# Rollo_APP_TS_V0_3.net
KiCad netlist of a schematic drawn in EAGLE
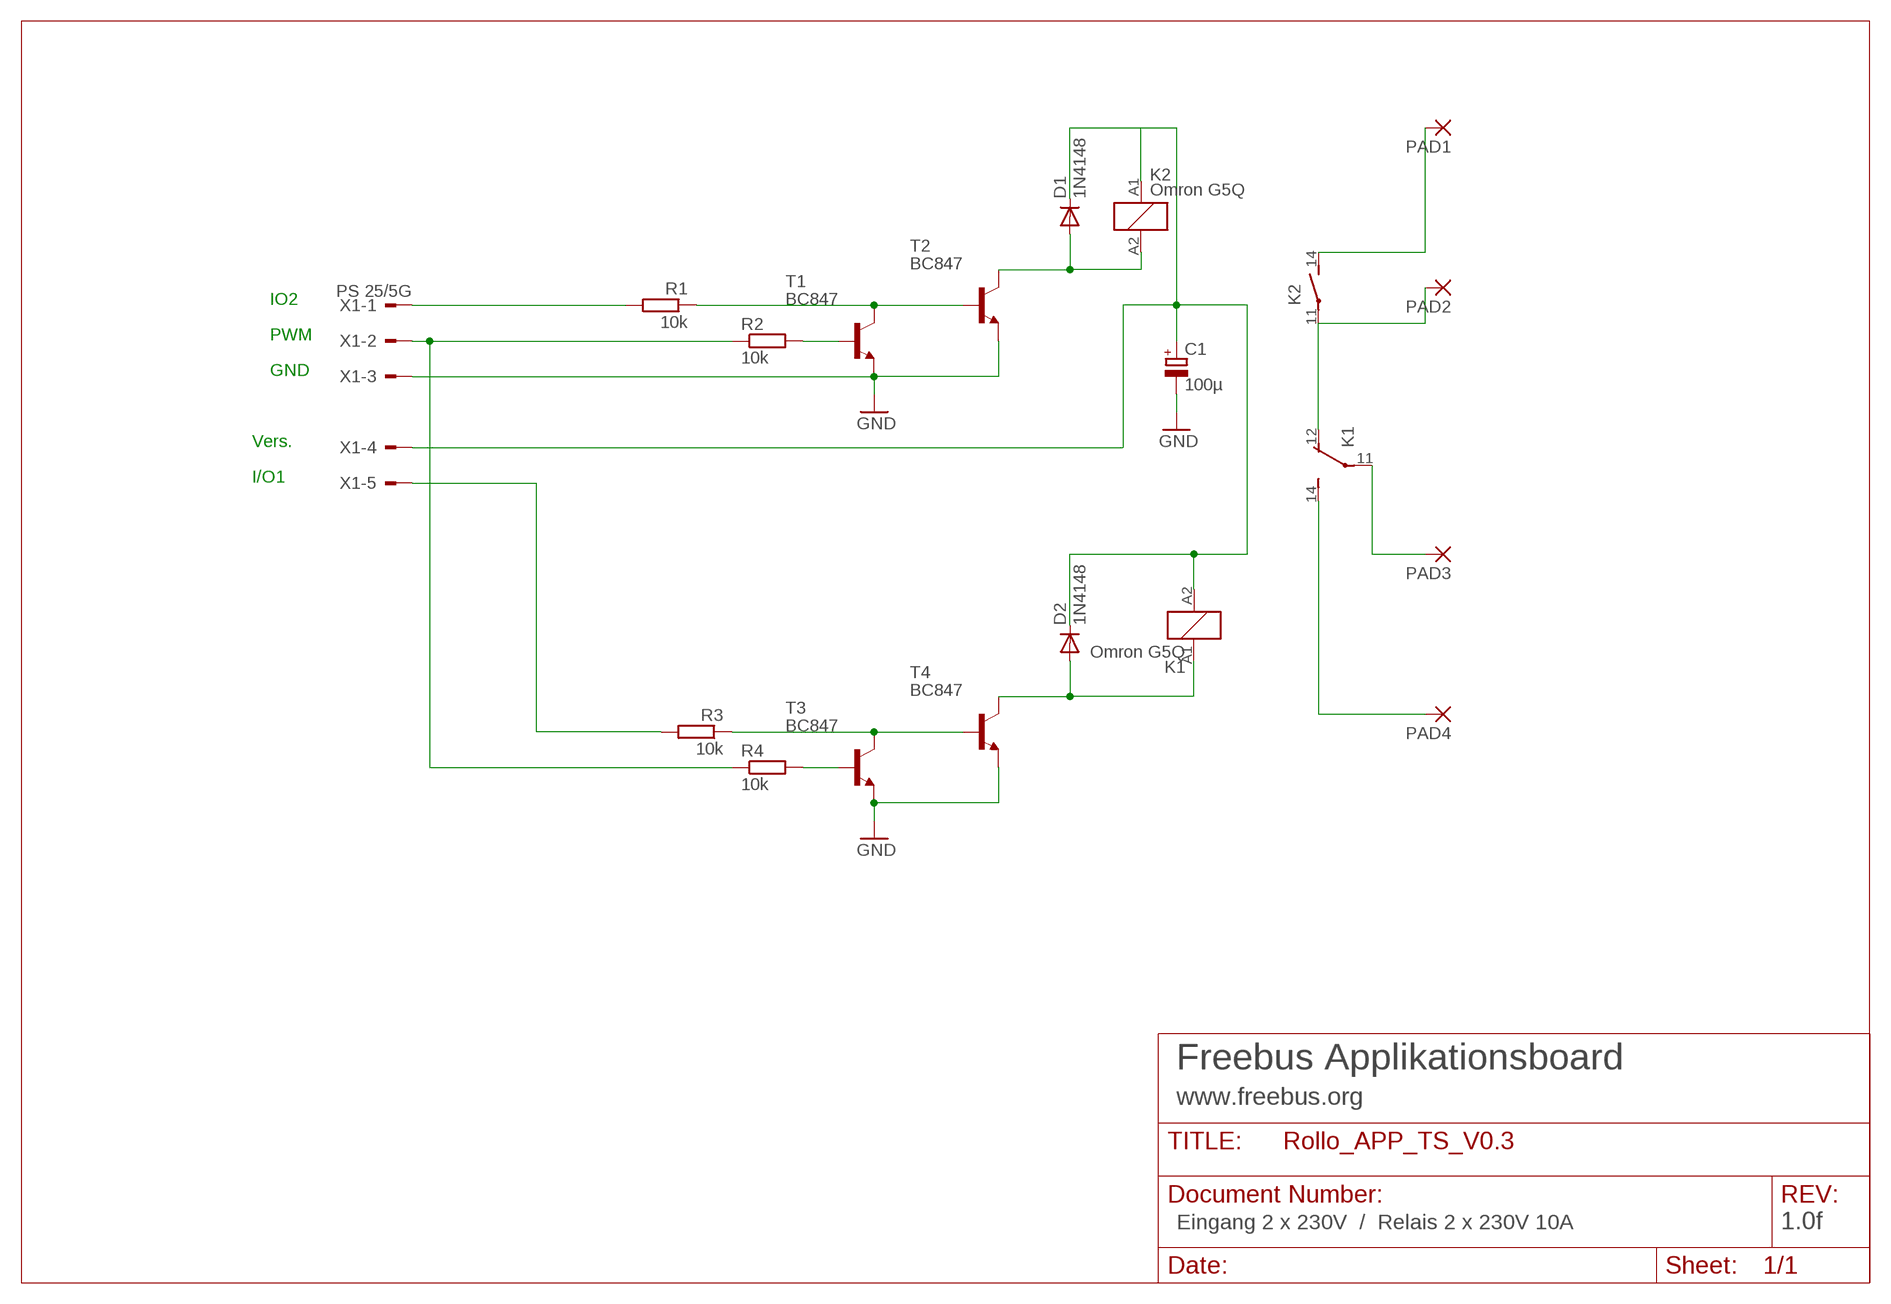
[diagram p0: schematic, sheet 1]

(export (version "E")
  (design (tool "Eeschema 10.0.6"))
  (components
    (comp (ref "C1")
      (value "100µ")
      (footprint "eagle-import:E3,5-8")
      (libsource (lib "eagle-import") (part "CPOL-EUE3.5-8"))
    )
    (comp (ref "D1")
      (value "1N4148")
      (footprint "eagle-import:MINIMELF")
      (libsource (lib "eagle-import") (part "DIODE-MINIMELF"))
    )
    (comp (ref "D2")
      (value "1N4148")
      (footprint "eagle-import:MINIMELF")
      (libsource (lib "eagle-import") (part "DIODE-MINIMELF"))
    )
    (comp (ref "K1")
      (value "Omron G5Q")
      (footprint "eagle-import:FREEBUS_RELAY_G5Q_1_EU")
      (libsource (lib "eagle-import") (part "FREEBUS_RELAY_RE03U"))
    )
    (comp (ref "K2")
      (value "Omron G5Q")
      (footprint "eagle-import:RE-SCHRACK")
      (fields (field (name "MF") "TYCO ELECTRONICS") (field (name "MPN") "RE030024"))
      (libsource (lib "eagle-import") (part "RE030024"))
    )
    (comp (ref "PAD1")
      (value "3,81/1,4")
      (footprint "eagle-import:3,81_1,4")
      (libsource (lib "eagle-import") (part "3,81/1,4"))
    )
    (comp (ref "PAD2")
      (value "3,81/1,4")
      (footprint "eagle-import:3,81_1,4")
      (libsource (lib "eagle-import") (part "3,81/1,4"))
    )
    (comp (ref "PAD3")
      (value "3,81/1,4")
      (footprint "eagle-import:3,81_1,4")
      (libsource (lib "eagle-import") (part "3,81/1,4"))
    )
    (comp (ref "PAD4")
      (value "3,81/1,4")
      (footprint "eagle-import:3,81_1,4")
      (libsource (lib "eagle-import") (part "3,81/1,4"))
    )
    (comp (ref "R1")
      (value "10k")
      (footprint "eagle-import:M1206")
      (libsource (lib "eagle-import") (part "R-EU_M1206"))
    )
    (comp (ref "R2")
      (value "10k")
      (footprint "eagle-import:M1206")
      (libsource (lib "eagle-import") (part "R-EU_M1206"))
    )
    (comp (ref "R3")
      (value "10k")
      (footprint "eagle-import:M1206")
      (libsource (lib "eagle-import") (part "R-EU_M1206"))
    )
    (comp (ref "R4")
      (value "10k")
      (footprint "eagle-import:M1206")
      (libsource (lib "eagle-import") (part "R-EU_M1206"))
    )
    (comp (ref "T1")
      (value "BC847")
      (footprint "eagle-import:SOT23")
      (libsource (lib "eagle-import") (part "BC847"))
    )
    (comp (ref "T2")
      (value "BC847")
      (footprint "eagle-import:SOT23")
      (libsource (lib "eagle-import") (part "BC847"))
    )
    (comp (ref "T3")
      (value "BC847")
      (footprint "eagle-import:SOT23")
      (libsource (lib "eagle-import") (part "BC847"))
    )
    (comp (ref "T4")
      (value "BC847")
      (footprint "eagle-import:SOT23")
      (libsource (lib "eagle-import") (part "BC847"))
    )
    (comp (ref "X1")
      (value "PS 25/5G")
      (footprint "eagle-import:741256-49")
      (libsource (lib "eagle-import") (part "741256-49"))
    )
  )
  (nets
    (net (code "1") (name "GND") (class "Default")
      (node (ref "C1") (pin "-") (pinfunction "-_-") (pintype "passive"))
      (node (ref "T1") (pin "2") (pinfunction "E_2") (pintype "passive"))
      (node (ref "T2") (pin "2") (pinfunction "E_2") (pintype "passive"))
      (node (ref "T3") (pin "2") (pinfunction "E_2") (pintype "passive"))
      (node (ref "T4") (pin "2") (pinfunction "E_2") (pintype "passive"))
      (node (ref "X1") (pin "3") (pinfunction "KL_3") (pintype "passive"))
    )
    (net (code "2") (name "Net-(K1A-O)") (class "Default")
      (node (ref "K1") (pin "12") (pinfunction "O_12") (pintype "passive"))
      (node (ref "K2") (pin "11") (pinfunction "P_11") (pintype "passive"))
      (node (ref "PAD2") (pin "1") (pinfunction "P_1") (pintype "passive"))
    )
    (net (code "3") (name "Net-(K1A-P)") (class "Default")
      (node (ref "K1") (pin "11") (pinfunction "P_11") (pintype "passive"))
      (node (ref "PAD3") (pin "1") (pinfunction "P_1") (pintype "passive"))
    )
    (net (code "4") (name "Net-(K1A-S)") (class "Default")
      (node (ref "K1") (pin "14") (pinfunction "S_14") (pintype "passive"))
      (node (ref "PAD4") (pin "1") (pinfunction "P_1") (pintype "passive"))
    )
    (net (code "5") (name "Net-(K1B-1)") (class "Default")
      (node (ref "D2") (pin "A") (pinfunction "A_A") (pintype "passive"))
      (node (ref "K1") (pin "A1") (pinfunction "1_A1") (pintype "passive"))
      (node (ref "T4") (pin "3") (pinfunction "C_3") (pintype "passive"))
    )
    (net (code "6") (name "Net-(K1B-2)") (class "Default")
      (node (ref "C1") (pin "+") (pinfunction "+_+") (pintype "passive"))
      (node (ref "D1") (pin "C") (pinfunction "C_C") (pintype "passive"))
      (node (ref "D2") (pin "C") (pinfunction "C_C") (pintype "passive"))
      (node (ref "K1") (pin "A2") (pinfunction "2_A2") (pintype "passive"))
      (node (ref "K2") (pin "A1") (pinfunction "1_A1") (pintype "passive"))
      (node (ref "X1") (pin "4") (pinfunction "KL_4") (pintype "passive"))
    )
    (net (code "7") (name "Net-(K2A-2)") (class "Default")
      (node (ref "D1") (pin "A") (pinfunction "A_A") (pintype "passive"))
      (node (ref "K2") (pin "A2") (pinfunction "2_A2") (pintype "passive"))
      (node (ref "T2") (pin "3") (pinfunction "C_3") (pintype "passive"))
    )
    (net (code "8") (name "Net-(K2B-S)") (class "Default")
      (node (ref "K2") (pin "14") (pinfunction "S_14") (pintype "passive"))
      (node (ref "PAD1") (pin "1") (pinfunction "P_1") (pintype "passive"))
    )
    (net (code "9") (name "Net-(T1-B)") (class "Default")
      (node (ref "R2") (pin "2") (pinfunction "2_2") (pintype "passive"))
      (node (ref "T1") (pin "1") (pinfunction "B_1") (pintype "passive"))
    )
    (net (code "10") (name "Net-(T1-C)") (class "Default")
      (node (ref "R1") (pin "1") (pinfunction "1_1") (pintype "passive"))
      (node (ref "T1") (pin "3") (pinfunction "C_3") (pintype "passive"))
      (node (ref "T2") (pin "1") (pinfunction "B_1") (pintype "passive"))
    )
    (net (code "11") (name "Net-(T3-B)") (class "Default")
      (node (ref "R4") (pin "2") (pinfunction "2_2") (pintype "passive"))
      (node (ref "T3") (pin "1") (pinfunction "B_1") (pintype "passive"))
    )
    (net (code "12") (name "Net-(T3-C)") (class "Default")
      (node (ref "R3") (pin "1") (pinfunction "1_1") (pintype "passive"))
      (node (ref "T3") (pin "3") (pinfunction "C_3") (pintype "passive"))
      (node (ref "T4") (pin "1") (pinfunction "B_1") (pintype "passive"))
    )
    (net (code "13") (name "Net-(X1A-KL)") (class "Default")
      (node (ref "R1") (pin "2") (pinfunction "2_2") (pintype "passive"))
      (node (ref "X1") (pin "1") (pinfunction "KL_1") (pintype "passive"))
    )
    (net (code "14") (name "Net-(X1B-KL)") (class "Default")
      (node (ref "R2") (pin "1") (pinfunction "1_1") (pintype "passive"))
      (node (ref "R4") (pin "1") (pinfunction "1_1") (pintype "passive"))
      (node (ref "X1") (pin "2") (pinfunction "KL_2") (pintype "passive"))
    )
    (net (code "15") (name "Net-(X1E-KL)") (class "Default")
      (node (ref "R3") (pin "2") (pinfunction "2_2") (pintype "passive"))
      (node (ref "X1") (pin "5") (pinfunction "KL_5") (pintype "passive"))
    )
  )
)
